# encoder-switch-type2-smd.net
KiCad netlist of a schematic drawn in EAGLE
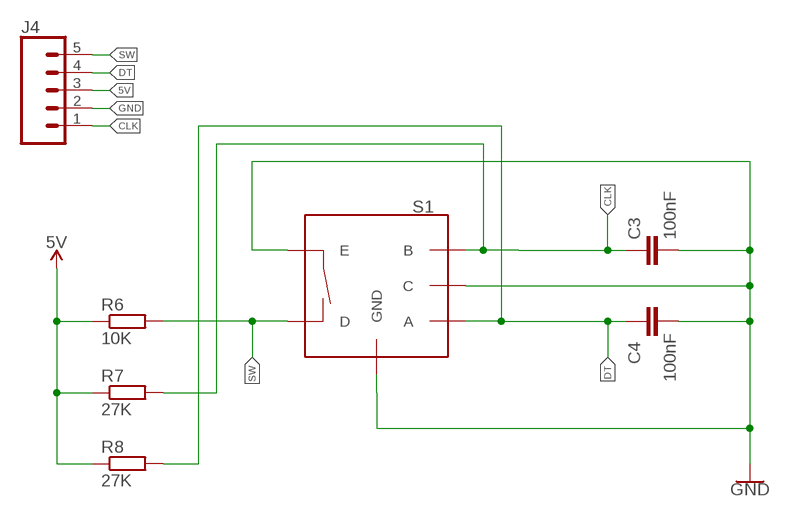
[diagram p0: schematic, sheet 1]

(export (version "E")
  (design (tool "Eeschema 10.0.6"))
  (components
    (comp (ref "C3")
      (value "100nF")
      (footprint "eagle-import:C1206")
      (libsource (lib "eagle-import") (part "C-EUC1206"))
    )
    (comp (ref "C4")
      (value "100nF")
      (footprint "eagle-import:C1206")
      (libsource (lib "eagle-import") (part "C-EUC1206"))
    )
    (comp (ref "J4")
      (value "CONN_051X05LA")
      (footprint "eagle-import:1X05_90")
      (libsource (lib "eagle-import") (part "CONN_051X05LA"))
    )
    (comp (ref "R6")
      (value "10K")
      (footprint "eagle-import:R1206")
      (libsource (lib "eagle-import") (part "R-EU_R1206"))
    )
    (comp (ref "R7")
      (value "27K")
      (footprint "eagle-import:R1206")
      (libsource (lib "eagle-import") (part "R-EU_R1206"))
    )
    (comp (ref "R8")
      (value "27K")
      (footprint "eagle-import:R1206")
      (libsource (lib "eagle-import") (part "R-EU_R1206"))
    )
    (comp (ref "S1")
      (value "ENCODER_SWITCH")
      (footprint "eagle-import:ROTARY_ENC_PLAIN")
      (libsource (lib "eagle-import") (part "ENCODER_SWITCH"))
    )
  )
  (nets
    (net (code "1") (name "5V") (class "Default")
      (node (ref "J4") (pin "3") (pinfunction "3_3") (pintype "passive"))
      (node (ref "R6") (pin "1") (pinfunction "1_1") (pintype "passive"))
      (node (ref "R7") (pin "1") (pinfunction "1_1") (pintype "passive"))
      (node (ref "R8") (pin "1") (pinfunction "1_1") (pintype "passive"))
    )
    (net (code "2") (name "CLK") (class "Default")
      (node (ref "C3") (pin "1") (pinfunction "1_1") (pintype "passive"))
      (node (ref "J4") (pin "1") (pinfunction "1_1") (pintype "passive"))
      (node (ref "R7") (pin "2") (pinfunction "2_2") (pintype "passive"))
      (node (ref "S1") (pin "B") (pinfunction "B_B") (pintype "bidirectional"))
    )
    (net (code "3") (name "DT") (class "Default")
      (node (ref "C4") (pin "1") (pinfunction "1_1") (pintype "passive"))
      (node (ref "J4") (pin "4") (pinfunction "4_4") (pintype "passive"))
      (node (ref "R8") (pin "2") (pinfunction "2_2") (pintype "passive"))
      (node (ref "S1") (pin "A") (pinfunction "A_A") (pintype "bidirectional"))
    )
    (net (code "4") (name "GND") (class "Default")
      (node (ref "C3") (pin "2") (pinfunction "2_2") (pintype "passive"))
      (node (ref "C4") (pin "2") (pinfunction "2_2") (pintype "passive"))
      (node (ref "J4") (pin "2") (pinfunction "2_2") (pintype "passive"))
      (node (ref "S1") (pin "C") (pinfunction "C_C") (pintype "bidirectional"))
      (node (ref "S1") (pin "E") (pinfunction "E_E") (pintype "bidirectional"))
      (node (ref "S1") (pin "GND1") (pinfunction "GND_GND1") (pintype "bidirectional"))
      (node (ref "S1") (pin "GND2") (pinfunction "GND_GND2") (pintype "bidirectional"))
    )
    (net (code "5") (name "SW") (class "Default")
      (node (ref "J4") (pin "5") (pinfunction "5_5") (pintype "passive"))
      (node (ref "R6") (pin "2") (pinfunction "2_2") (pintype "passive"))
      (node (ref "S1") (pin "D") (pinfunction "D_D") (pintype "bidirectional"))
    )
  )
)
